# frets-main-board2.net
KiCad netlist of a schematic drawn in EAGLE
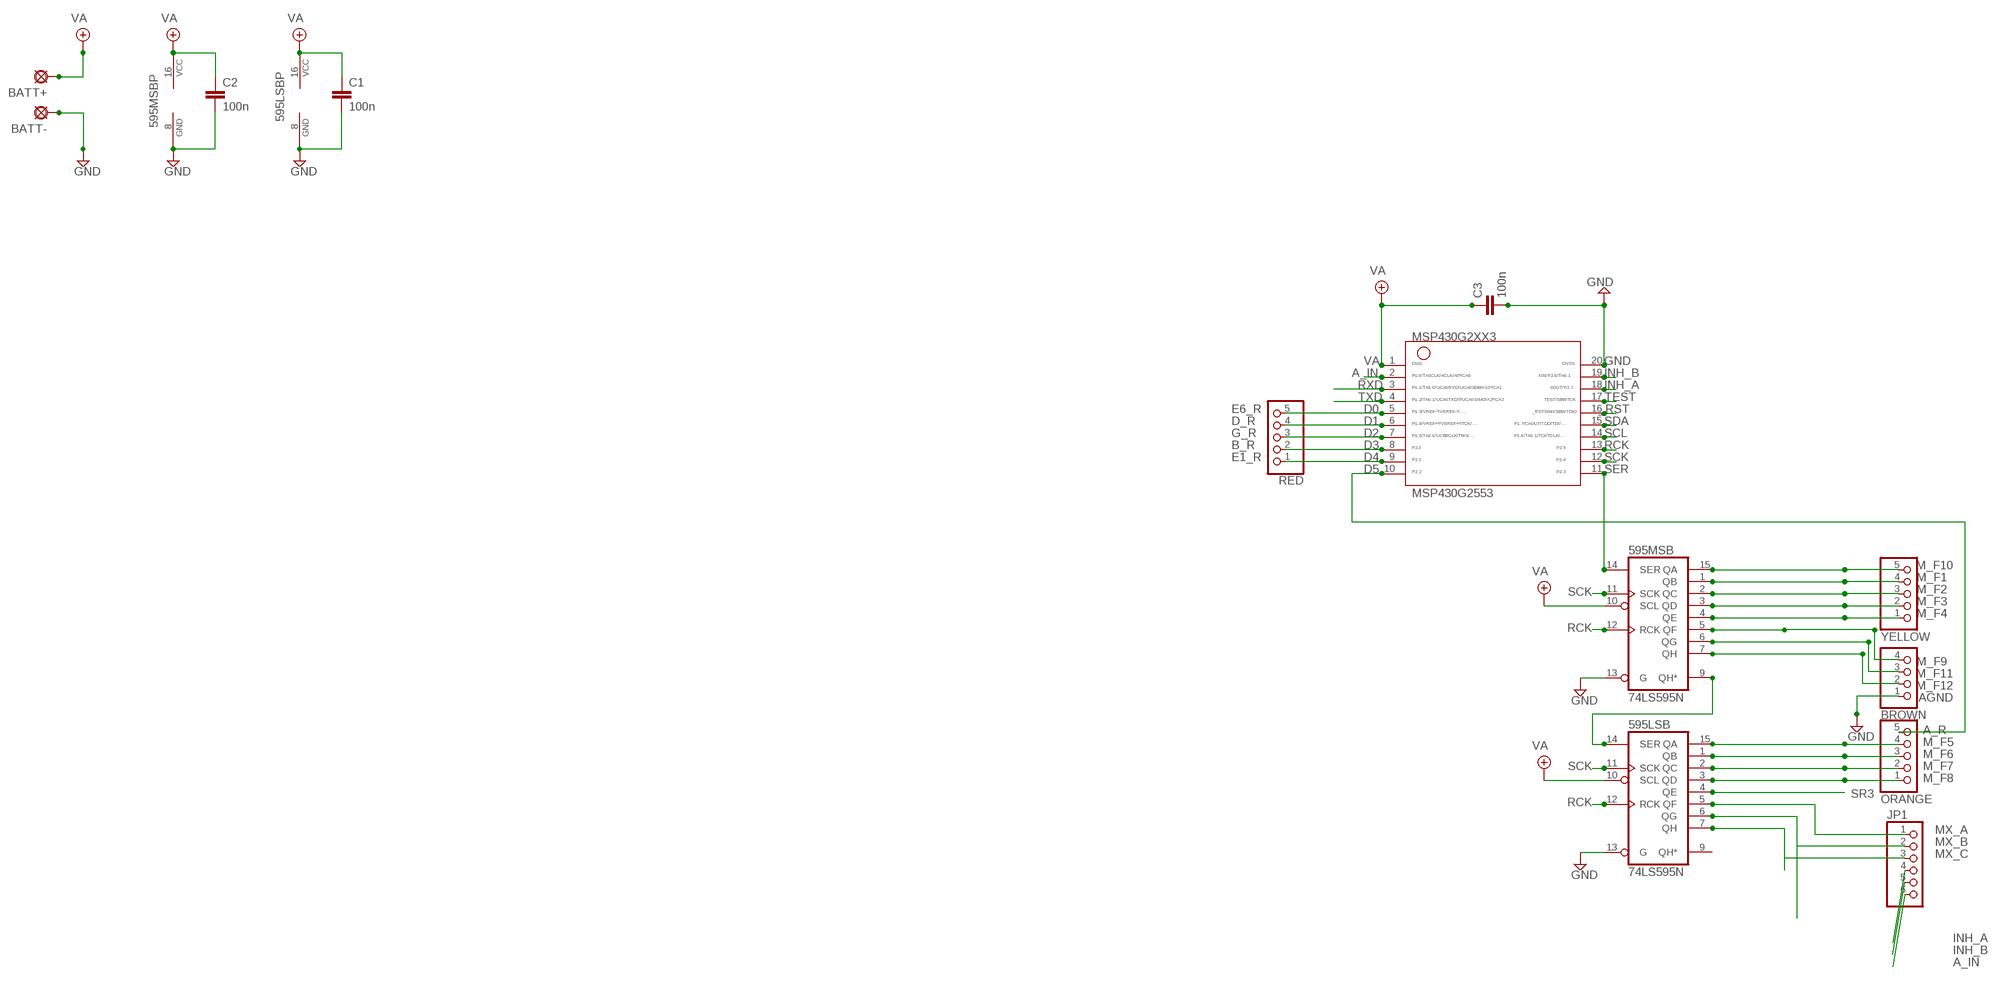
[diagram p0: schematic, sheet 1]

(export (version "E")
  (design (tool "Eeschema 10.0.6"))
  (components
    (comp (ref "595LSB")
      (value "74LS595N")
      (footprint "eagle-import:DIL16")
      (libsource (lib "eagle-import") (part "74595NLS"))
    )
    (comp (ref "595MSB")
      (value "74LS595N")
      (footprint "eagle-import:DIL16")
      (libsource (lib "eagle-import") (part "74595NLS"))
    )
    (comp (ref "BATT+")
      (value "PADL")
      (footprint "eagle-import:LONG")
      (libsource (lib "eagle-import") (part "PADL"))
    )
    (comp (ref "BATT-")
      (value "PADL")
      (footprint "eagle-import:LONG")
      (libsource (lib "eagle-import") (part "PADL"))
    )
    (comp (ref "BROWN")
      (value "PINHD-1X4")
      (footprint "eagle-import:1X04")
      (libsource (lib "eagle-import") (part "PINHD-1X4"))
    )
    (comp (ref "C1")
      (value "100n")
      (footprint "eagle-import:050X030_050_3")
      (libsource (lib "eagle-import") (part "050X030_050"))
    )
    (comp (ref "C2")
      (value "100n")
      (footprint "eagle-import:050X030_050_3")
      (libsource (lib "eagle-import") (part "050X030_050"))
    )
    (comp (ref "C3")
      (value "100n")
      (footprint "eagle-import:050X030_050_3")
      (libsource (lib "eagle-import") (part "050X030_050"))
    )
    (comp (ref "JP1")
      (value "PINHD-1X6")
      (footprint "eagle-import:1X06")
      (libsource (lib "eagle-import") (part "PINHD-1X6"))
    )
    (comp (ref "MSP430G2553")
      (value "G2XX3---N20")
      (footprint "eagle-import:N20")
      (libsource (lib "eagle-import") (part "G2XX3---N20"))
    )
    (comp (ref "ORANGE")
      (value "PINHD-1X5")
      (footprint "eagle-import:1X05")
      (libsource (lib "eagle-import") (part "PINHD-1X5"))
    )
    (comp (ref "RED")
      (value "PINHD-1X5")
      (footprint "eagle-import:1X05")
      (libsource (lib "eagle-import") (part "PINHD-1X5"))
    )
    (comp (ref "YELLOW")
      (value "PINHD-1X5")
      (footprint "eagle-import:1X05")
      (libsource (lib "eagle-import") (part "PINHD-1X5"))
    )
  )
  (nets
    (net (code "1") (name "/A_IN") (class "Default")
      (node (ref "JP1") (pin "6") (pinfunction "6_6") (pintype "passive"))
      (node (ref "MSP430G2553") (pin "2") (pinfunction "2_2") (pintype "bidirectional"))
    )
    (net (code "2") (name "/D0") (class "Default")
      (node (ref "MSP430G2553") (pin "5") (pinfunction "5_5") (pintype "bidirectional"))
      (node (ref "RED") (pin "5") (pinfunction "5_5") (pintype "passive"))
    )
    (net (code "3") (name "/D1") (class "Default")
      (node (ref "MSP430G2553") (pin "6") (pinfunction "6_6") (pintype "bidirectional"))
      (node (ref "RED") (pin "4") (pinfunction "4_4") (pintype "passive"))
    )
    (net (code "4") (name "/D2") (class "Default")
      (node (ref "MSP430G2553") (pin "7") (pinfunction "7_7") (pintype "bidirectional"))
      (node (ref "RED") (pin "3") (pinfunction "3_3") (pintype "passive"))
    )
    (net (code "5") (name "/D3") (class "Default")
      (node (ref "MSP430G2553") (pin "8") (pinfunction "8_8") (pintype "bidirectional"))
      (node (ref "RED") (pin "2") (pinfunction "2_2") (pintype "passive"))
    )
    (net (code "6") (name "/D4") (class "Default")
      (node (ref "MSP430G2553") (pin "9") (pinfunction "9_9") (pintype "bidirectional"))
      (node (ref "RED") (pin "1") (pinfunction "1_1") (pintype "passive"))
    )
    (net (code "7") (name "/D5") (class "Default")
      (node (ref "MSP430G2553") (pin "10") (pinfunction "10_10") (pintype "bidirectional"))
      (node (ref "ORANGE") (pin "5") (pinfunction "5_5") (pintype "passive"))
    )
    (net (code "8") (name "/INH_A") (class "Default")
      (node (ref "JP1") (pin "4") (pinfunction "4_4") (pintype "passive"))
      (node (ref "MSP430G2553") (pin "18") (pinfunction "18_18") (pintype "bidirectional"))
    )
    (net (code "9") (name "/INH_B") (class "Default")
      (node (ref "JP1") (pin "5") (pinfunction "5_5") (pintype "passive"))
      (node (ref "MSP430G2553") (pin "19") (pinfunction "19_19") (pintype "bidirectional"))
    )
    (net (code "10") (name "/MX_A") (class "Default")
      (node (ref "595LSB") (pin "5") (pinfunction "QF_5") (pintype "tri_state"))
      (node (ref "JP1") (pin "1") (pinfunction "1_1") (pintype "passive"))
    )
    (net (code "11") (name "/MX_B") (class "Default")
      (node (ref "595LSB") (pin "6") (pinfunction "QG_6") (pintype "tri_state"))
      (node (ref "JP1") (pin "2") (pinfunction "2_2") (pintype "passive"))
    )
    (net (code "12") (name "/MX_C") (class "Default")
      (node (ref "595LSB") (pin "7") (pinfunction "QH_7") (pintype "tri_state"))
      (node (ref "JP1") (pin "3") (pinfunction "3_3") (pintype "passive"))
    )
    (net (code "13") (name "/RCK") (class "Default")
      (node (ref "595LSB") (pin "12") (pinfunction "RCK_12") (pintype "input"))
      (node (ref "595MSB") (pin "12") (pinfunction "RCK_12") (pintype "input"))
      (node (ref "MSP430G2553") (pin "13") (pinfunction "13_13") (pintype "bidirectional"))
    )
    (net (code "14") (name "/RXD") (class "Default")
      (node (ref "MSP430G2553") (pin "3") (pinfunction "3_3") (pintype "bidirectional"))
    )
    (net (code "15") (name "/SCK") (class "Default")
      (node (ref "595LSB") (pin "11") (pinfunction "SCK_11") (pintype "input"))
      (node (ref "595MSB") (pin "11") (pinfunction "SCK_11") (pintype "input"))
      (node (ref "MSP430G2553") (pin "12") (pinfunction "12_12") (pintype "bidirectional"))
    )
    (net (code "16") (name "/SCL") (class "Default")
      (node (ref "MSP430G2553") (pin "14") (pinfunction "14_14") (pintype "bidirectional"))
    )
    (net (code "17") (name "/SDA") (class "Default")
      (node (ref "MSP430G2553") (pin "15") (pinfunction "15_15") (pintype "bidirectional"))
    )
    (net (code "18") (name "/SER") (class "Default")
      (node (ref "595MSB") (pin "14") (pinfunction "SER_14") (pintype "input"))
      (node (ref "MSP430G2553") (pin "11") (pinfunction "11_11") (pintype "bidirectional"))
    )
    (net (code "19") (name "/SR3") (class "Default")
      (node (ref "595LSB") (pin "4") (pinfunction "QE_4") (pintype "tri_state"))
    )
    (net (code "20") (name "/TEST") (class "Default")
      (node (ref "MSP430G2553") (pin "17") (pinfunction "17_17") (pintype "bidirectional"))
    )
    (net (code "21") (name "/TXD") (class "Default")
      (node (ref "MSP430G2553") (pin "4") (pinfunction "4_4") (pintype "bidirectional"))
    )
    (net (code "22") (name "/_RST") (class "Default")
      (node (ref "MSP430G2553") (pin "16") (pinfunction "16_16") (pintype "bidirectional"))
    )
    (net (code "23") (name "GND") (class "Default")
      (node (ref "595LSB") (pin "13") (pinfunction "G_13") (pintype "input"))
      (node (ref "595LSB") (pin "8") (pinfunction "GND_8") (pintype "power_in"))
      (node (ref "595MSB") (pin "13") (pinfunction "G_13") (pintype "input"))
      (node (ref "595MSB") (pin "8") (pinfunction "GND_8") (pintype "power_in"))
      (node (ref "BATT-") (pin "1") (pinfunction "PAD_1") (pintype "passive"))
      (node (ref "BROWN") (pin "1") (pinfunction "1_1") (pintype "passive"))
      (node (ref "C1") (pin "2") (pinfunction "2_2") (pintype "passive"))
      (node (ref "C2") (pin "2") (pinfunction "2_2") (pintype "passive"))
      (node (ref "C3") (pin "2") (pinfunction "2_2") (pintype "passive"))
      (node (ref "MSP430G2553") (pin "20") (pinfunction "20_20") (pintype "bidirectional"))
    )
    (net (code "24") (name "Net-(595LSBA-QA)") (class "Default")
      (node (ref "595LSB") (pin "15") (pinfunction "QA_15") (pintype "tri_state"))
      (node (ref "ORANGE") (pin "4") (pinfunction "4_4") (pintype "passive"))
    )
    (net (code "25") (name "Net-(595LSBA-QB)") (class "Default")
      (node (ref "595LSB") (pin "1") (pinfunction "QB_1") (pintype "tri_state"))
      (node (ref "ORANGE") (pin "3") (pinfunction "3_3") (pintype "passive"))
    )
    (net (code "26") (name "Net-(595LSBA-QC)") (class "Default")
      (node (ref "595LSB") (pin "2") (pinfunction "QC_2") (pintype "tri_state"))
      (node (ref "ORANGE") (pin "2") (pinfunction "2_2") (pintype "passive"))
    )
    (net (code "27") (name "Net-(595LSBA-QD)") (class "Default")
      (node (ref "595LSB") (pin "3") (pinfunction "QD_3") (pintype "tri_state"))
      (node (ref "ORANGE") (pin "1") (pinfunction "1_1") (pintype "passive"))
    )
    (net (code "28") (name "Net-(595LSBA-SER)") (class "Default")
      (node (ref "595LSB") (pin "14") (pinfunction "SER_14") (pintype "input"))
      (node (ref "595MSB") (pin "9") (pinfunction "QH*_9") (pintype "tri_state"))
    )
    (net (code "29") (name "Net-(595MSBA-QA)") (class "Default")
      (node (ref "595MSB") (pin "15") (pinfunction "QA_15") (pintype "tri_state"))
      (node (ref "YELLOW") (pin "5") (pinfunction "5_5") (pintype "passive"))
    )
    (net (code "30") (name "Net-(595MSBA-QB)") (class "Default")
      (node (ref "595MSB") (pin "1") (pinfunction "QB_1") (pintype "tri_state"))
      (node (ref "YELLOW") (pin "4") (pinfunction "4_4") (pintype "passive"))
    )
    (net (code "31") (name "Net-(595MSBA-QC)") (class "Default")
      (node (ref "595MSB") (pin "2") (pinfunction "QC_2") (pintype "tri_state"))
      (node (ref "YELLOW") (pin "3") (pinfunction "3_3") (pintype "passive"))
    )
    (net (code "32") (name "Net-(595MSBA-QD)") (class "Default")
      (node (ref "595MSB") (pin "3") (pinfunction "QD_3") (pintype "tri_state"))
      (node (ref "YELLOW") (pin "2") (pinfunction "2_2") (pintype "passive"))
    )
    (net (code "33") (name "Net-(595MSBA-QE)") (class "Default")
      (node (ref "595MSB") (pin "4") (pinfunction "QE_4") (pintype "tri_state"))
      (node (ref "YELLOW") (pin "1") (pinfunction "1_1") (pintype "passive"))
    )
    (net (code "34") (name "Net-(595MSBA-QF)") (class "Default")
      (node (ref "595MSB") (pin "5") (pinfunction "QF_5") (pintype "tri_state"))
      (node (ref "BROWN") (pin "4") (pinfunction "4_4") (pintype "passive"))
    )
    (net (code "35") (name "Net-(595MSBA-QG)") (class "Default")
      (node (ref "595MSB") (pin "6") (pinfunction "QG_6") (pintype "tri_state"))
      (node (ref "BROWN") (pin "3") (pinfunction "3_3") (pintype "passive"))
    )
    (net (code "36") (name "Net-(595MSBA-QH)") (class "Default")
      (node (ref "595MSB") (pin "7") (pinfunction "QH_7") (pintype "tri_state"))
      (node (ref "BROWN") (pin "2") (pinfunction "2_2") (pintype "passive"))
    )
    (net (code "37") (name "VA") (class "Default")
      (node (ref "595LSB") (pin "10") (pinfunction "SCL_10") (pintype "input"))
      (node (ref "595LSB") (pin "16") (pinfunction "VCC_16") (pintype "power_in"))
      (node (ref "595MSB") (pin "10") (pinfunction "SCL_10") (pintype "input"))
      (node (ref "595MSB") (pin "16") (pinfunction "VCC_16") (pintype "power_in"))
      (node (ref "BATT+") (pin "1") (pinfunction "PAD_1") (pintype "passive"))
      (node (ref "C1") (pin "1") (pinfunction "1_1") (pintype "passive"))
      (node (ref "C2") (pin "1") (pinfunction "1_1") (pintype "passive"))
      (node (ref "C3") (pin "1") (pinfunction "1_1") (pintype "passive"))
      (node (ref "MSP430G2553") (pin "1") (pinfunction "1_1") (pintype "bidirectional"))
    )
    (net (code "38") (name "unconnected-(595LSBA-QH*-Pad9)") (class "Default")
      (node (ref "595LSB") (pin "9") (pinfunction "QH*_9") (pintype "tri_state"))
    )
  )
)
